# Fonte5V.net
KiCad netlist of a schematic drawn in Altium Designer
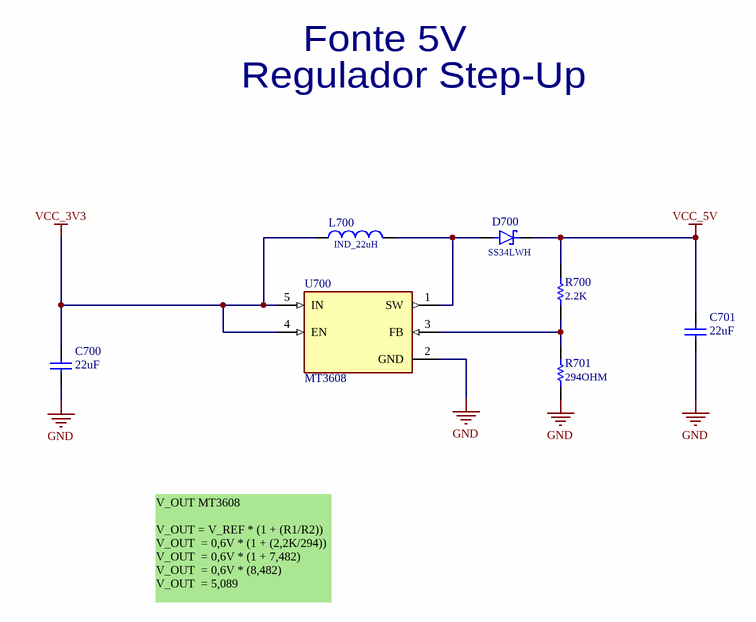
[diagram p0: Fonte5V.SchDoc]

(export (version "E")
  (design (tool "Eeschema 10.0.6"))
  (components
    (comp (ref "C700")
      (value "22uF")
      (footprint "CAP_CER_0603")
      (libsource (lib "PCB_TCC") (part "CAP_CER_22uF_0603"))
    )
    (comp (ref "C701")
      (value "22uF")
      (footprint "CAP_CER_0603")
      (libsource (lib "PCB_TCC") (part "CAP_CER_22uF_0603"))
    )
    (comp (ref "D700")
      (value "SS34LWH")
      (footprint "DIODE_SS34LWH")
      (libsource (lib "PCB_TCC") (part "DIODE_SS34LWH"))
    )
    (comp (ref "L700")
      (value "IND_22uH")
      (footprint "FIXED_IND_22uH")
      (libsource (lib "PCB_TCC") (part "FIXED_IND_22uH"))
    )
    (comp (ref "R700")
      (value "2.2K")
      (footprint "RES_0603")
      (libsource (lib "PCB_TCC") (part "RES_2.2K_0603"))
    )
    (comp (ref "R701") (value "294OHM") (libsource (lib "PCB_TCC") (part "RES_294OHM_0603")))
    (comp (ref "U700") (value "MT3608") (footprint "MT3608") (libsource (lib "PCB_TCC") (part "MT3608")))
  )
  (nets
    (net (code "1") (name "GND") (class "Default")
      (node (ref "C700") (pin "1") (pinfunction "1_1") (pintype "passive"))
      (node (ref "C701") (pin "1") (pinfunction "1_1") (pintype "passive"))
      (node (ref "R701") (pin "1") (pinfunction "1_1") (pintype "passive"))
      (node (ref "U700") (pin "2") (pinfunction "GND_2") (pintype "power_in"))
    )
    (net (code "2") (name "Net-(U700-FB)") (class "Default")
      (node (ref "R700") (pin "1") (pinfunction "1_1") (pintype "passive"))
      (node (ref "R701") (pin "2") (pinfunction "2_2") (pintype "passive"))
      (node (ref "U700") (pin "3") (pinfunction "FB_3") (pintype "input"))
    )
    (net (code "3") (name "Net-(U700-SW)") (class "Default")
      (node (ref "D700") (pin "A") (pinfunction "A_A") (pintype "passive"))
      (node (ref "L700") (pin "2") (pinfunction "2_2") (pintype "passive"))
      (node (ref "U700") (pin "1") (pinfunction "SW_1") (pintype "output"))
    )
    (net (code "4") (name "VCC_3V3") (class "Default")
      (node (ref "C700") (pin "2") (pinfunction "2_2") (pintype "passive"))
      (node (ref "L700") (pin "1") (pinfunction "1_1") (pintype "passive"))
      (node (ref "U700") (pin "4") (pinfunction "EN_4") (pintype "input"))
      (node (ref "U700") (pin "5") (pinfunction "IN_5") (pintype "input"))
    )
    (net (code "5") (name "VCC_5V") (class "Default")
      (node (ref "C701") (pin "2") (pinfunction "2_2") (pintype "passive"))
      (node (ref "D700") (pin "C") (pinfunction "K_C") (pintype "passive"))
      (node (ref "R700") (pin "2") (pinfunction "2_2") (pintype "passive"))
    )
  )
)
